# lowpass-adc-input.net
KiCad netlist of a schematic drawn in Altium Designer
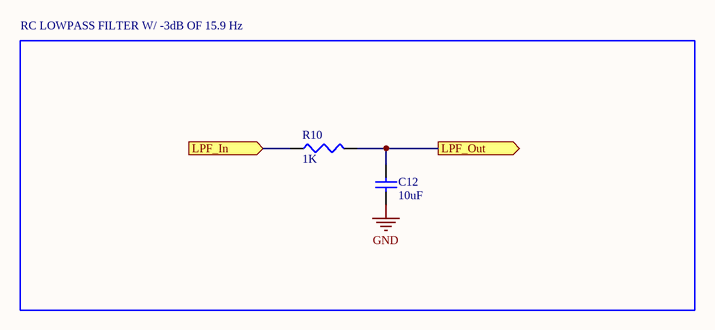
[diagram p0: lowpass-adc-input.SchDoc]

(export (version "E")
  (design (tool "Eeschema 10.0.6"))
  (components
    (comp (ref "C12")
      (value "10uF")
      (footprint "C1206")
      (description "Capacitor (Semiconductor SIM Model)")
      (fields (field (name "PUBLISHER") "Altium Limited"))
      (libsource (lib "Miscellaneous Devices") (part "Cap Semi"))
    )
    (comp (ref "R10")
      (value "1K")
      (footprint "J1-0603")
      (description "Resistor")
      (fields (field (name "PUBLISHER") "Altium Limited"))
      (libsource (lib "Miscellaneous Devices") (part "Res3"))
    )
  )
  (nets
    (net (code "1") (name "/LPF_In") (class "Default")
      (node (ref "R10") (pin "1") (pinfunction "1_1") (pintype "passive"))
    )
    (net (code "2") (name "/LPF_Out") (class "Default")
      (node (ref "C12") (pin "2") (pinfunction "2_2") (pintype "passive"))
      (node (ref "R10") (pin "2") (pinfunction "2_2") (pintype "passive"))
    )
    (net (code "3") (name "GND") (class "Default")
      (node (ref "C12") (pin "1") (pinfunction "1_1") (pintype "passive"))
    )
  )
)
